# Sheet2.net
KiCad netlist of a schematic drawn in Altium Designer
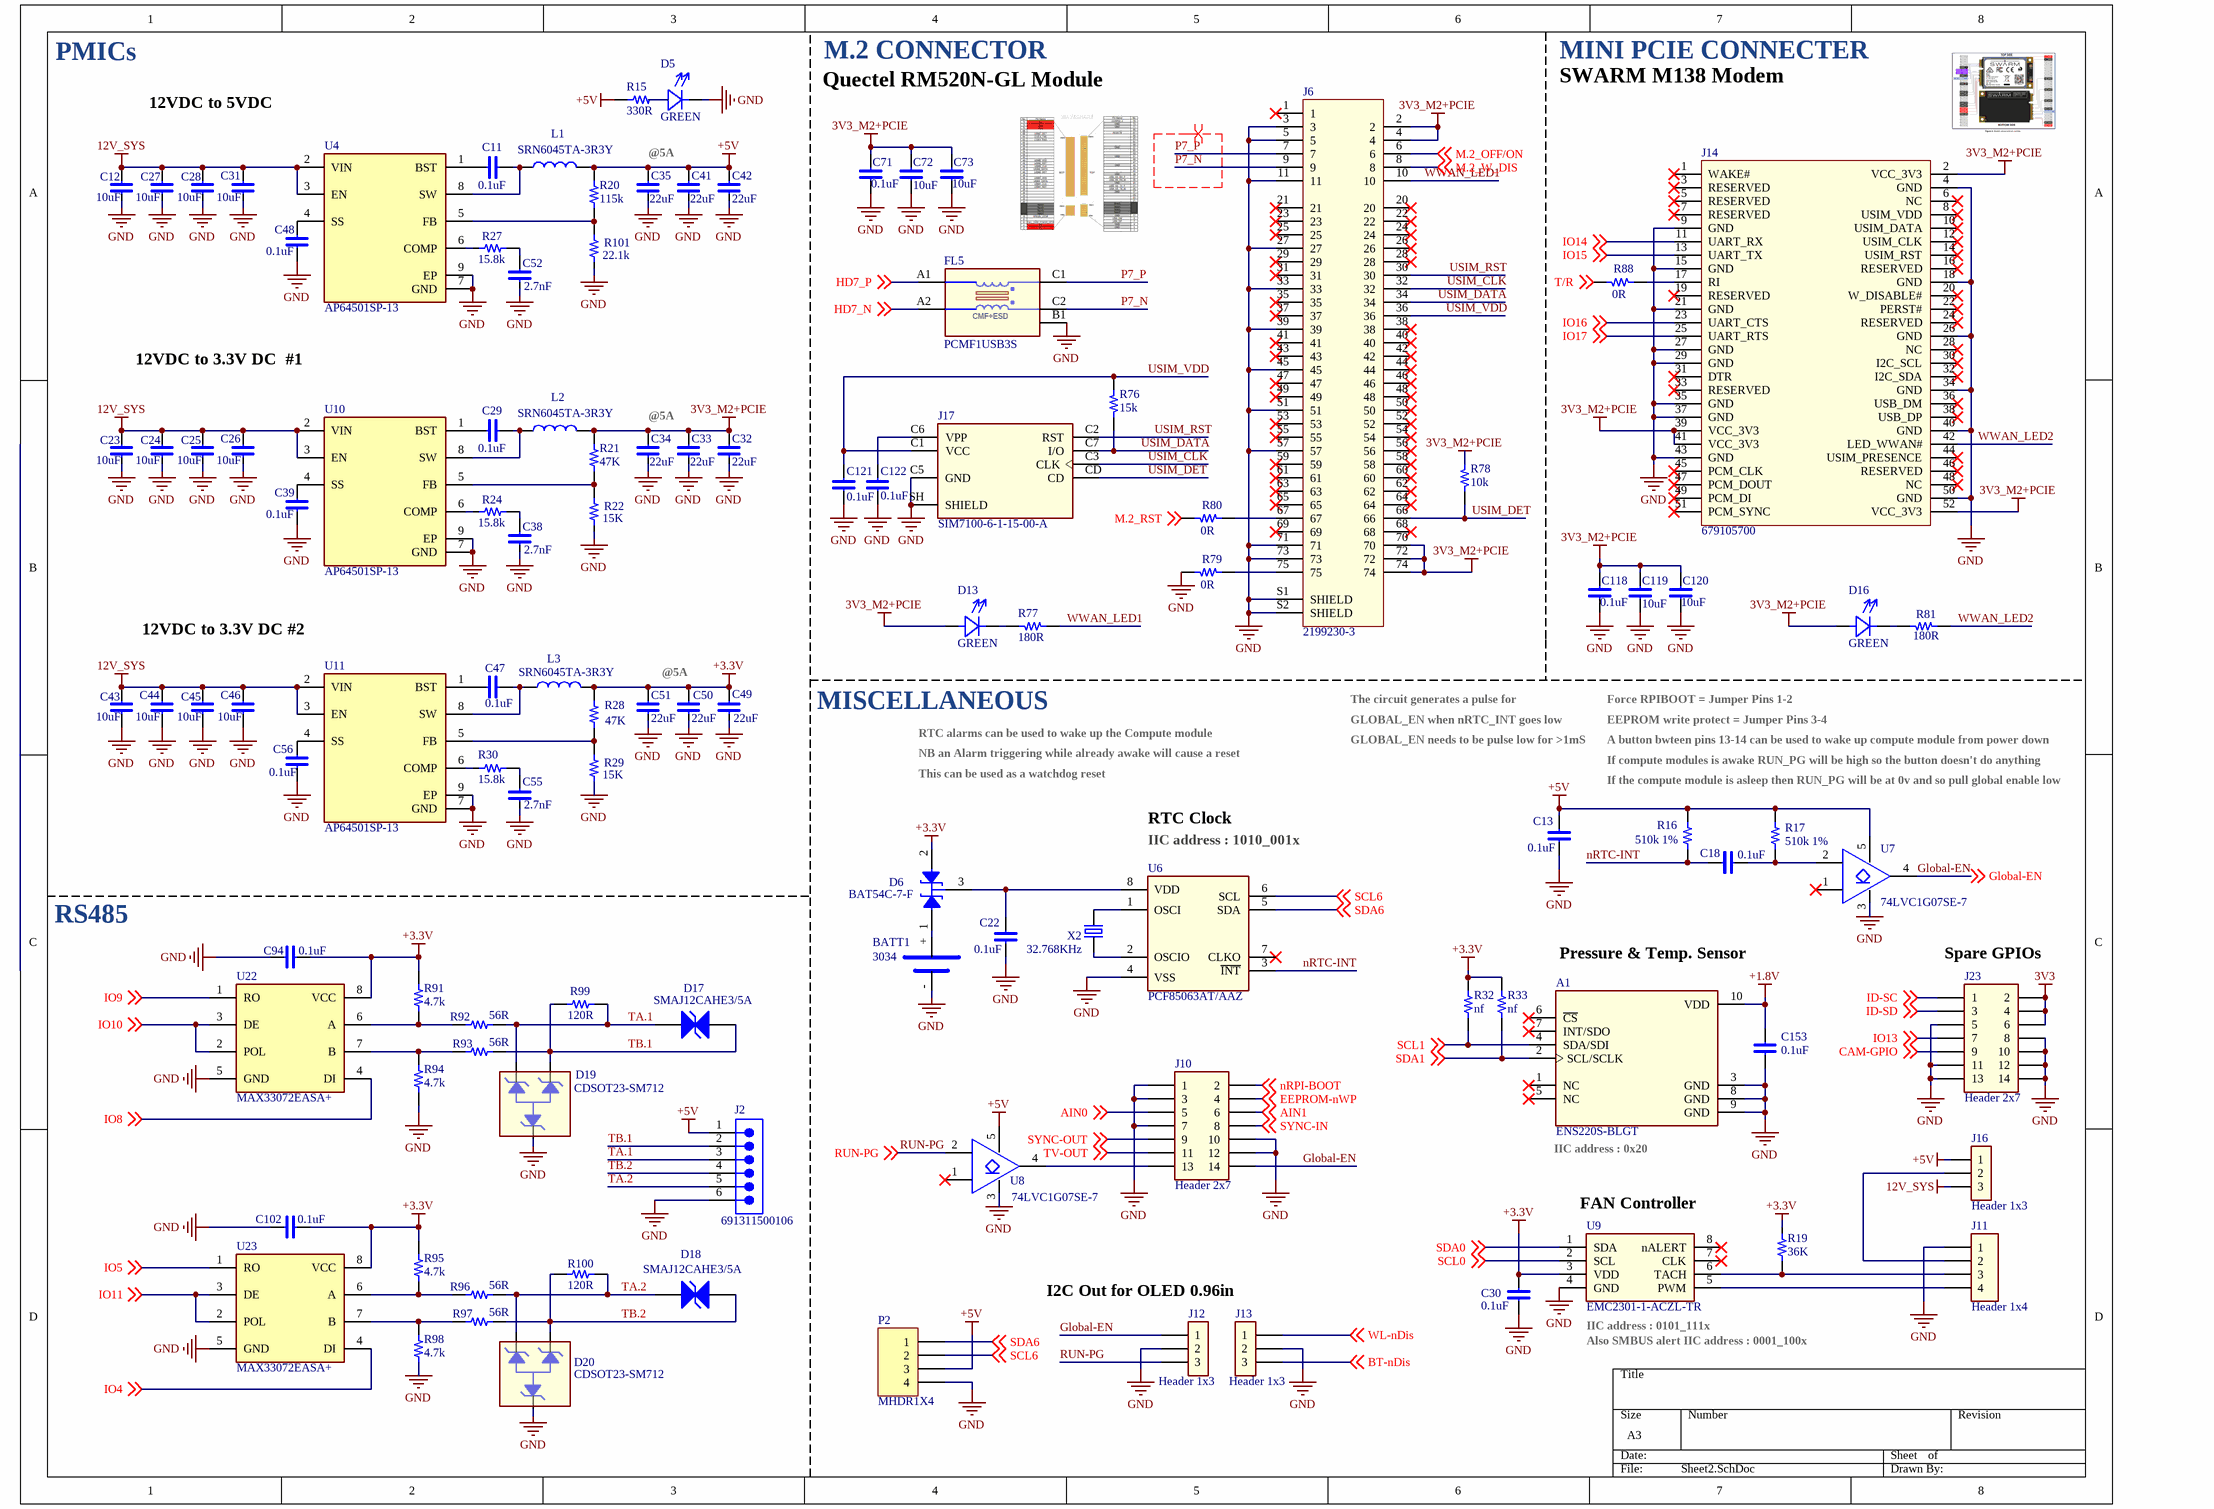
[diagram p0: Sheet2.SchDoc]

(export (version "E")
  (design (tool "Eeschema 10.0.6"))
  (components
    (comp (ref "A1")
      (value "ENS220S-BLGT")
      (footprint "XDCR_ENS220S-BLGT")
      (fields (field (name "MF") "ScioSense"))
      (libsource (lib "ENS220S-BLGT") (part "ENS220S-BLGT"))
    )
    (comp (ref "BATT1")
      (value "3034")
      (footprint "Keystone-3034")
      (description "BATTERY RETAINER COIN 20MM SMD")
      (libsource (lib "Custom_Library") (part "Coin-Cell"))
    )
    (comp (ref "C11")
      (value "0.1uF")
      (footprint "C-0402/1005")
      (description "CAP CER 10UF 25V X5R 1206")
      (fields (field (name "MFR. PART NO.") "C1206C106M3PACTU"))
      (libsource (lib "Custom_Library") (part "CAP 1206/3216"))
    )
    (comp (ref "C12")
      (value "10uF")
      (footprint "C-0805/2012")
      (description "CAP CER 10UF 25V X5R 1206")
      (fields (field (name "MFR. PART NO.") "C1206C106M3PACTU"))
      (libsource (lib "Custom_Library") (part "CAP 1206/3216"))
    )
    (comp (ref "C13")
      (value "0.1uF")
      (footprint "C-0402/1005")
      (description "CAP CER 0.1UF 16V X7R 0402")
      (fields (field (name "MFR. PART NO.") "GCM155R71C104KA55D"))
      (libsource (lib "Custom_Library") (part "Capacitor-NonPolar"))
    )
    (comp (ref "C18")
      (value "0.1uF")
      (footprint "C-0402/1005")
      (description "CAP CER 0.1UF 16V X7R 0402")
      (fields (field (name "MFR. PART NO.") "GCM155R71C104KA55D"))
      (libsource (lib "") (part "Capacitor-NonPolar_1"))
    )
    (comp (ref "C22")
      (value "0.1uF")
      (footprint "C-0402/1005")
      (description "CAP CER 0.1UF 16V X7R 0402")
      (fields (field (name "MFR. PART NO.") "GCM155R71C104KA55D"))
      (libsource (lib "Custom_Library") (part "Capacitor-NonPolar"))
    )
    (comp (ref "C23")
      (value "10uF")
      (footprint "C-0805/2012")
      (description "CAP CER 10UF 25V X5R 1206")
      (fields (field (name "MFR. PART NO.") "C1206C106M3PACTU"))
      (libsource (lib "Custom_Library") (part "CAP 1206/3216"))
    )
    (comp (ref "C24")
      (value "10uF")
      (footprint "C-0805/2012")
      (description "CAP CER 10UF 25V X5R 1206")
      (fields (field (name "MFR. PART NO.") "C1206C106M3PACTU"))
      (libsource (lib "Custom_Library") (part "CAP 1206/3216"))
    )
    (comp (ref "C25")
      (value "10uF")
      (footprint "C-0805/2012")
      (description "CAP CER 10UF 25V X5R 1206")
      (fields (field (name "MFR. PART NO.") "C1206C106M3PACTU"))
      (libsource (lib "Custom_Library") (part "CAP 1206/3216"))
    )
    (comp (ref "C26")
      (value "10uF")
      (footprint "C-0805/2012")
      (description "CAP CER 10UF 25V X5R 1206")
      (fields (field (name "MFR. PART NO.") "C1206C106M3PACTU"))
      (libsource (lib "Custom_Library") (part "CAP 1206/3216"))
    )
    (comp (ref "C27")
      (value "10uF")
      (footprint "C-0805/2012")
      (description "CAP CER 10UF 25V X5R 1206")
      (fields (field (name "MFR. PART NO.") "C1206C106M3PACTU"))
      (libsource (lib "Custom_Library") (part "CAP 1206/3216"))
    )
    (comp (ref "C28")
      (value "10uF")
      (footprint "C-0805/2012")
      (description "CAP CER 10UF 25V X5R 1206")
      (fields (field (name "MFR. PART NO.") "C1206C106M3PACTU"))
      (libsource (lib "Custom_Library") (part "CAP 1206/3216"))
    )
    (comp (ref "C29")
      (value "0.1uF")
      (footprint "C-0402/1005")
      (description "CAP CER 10UF 25V X5R 1206")
      (fields (field (name "MFR. PART NO.") "C1206C106M3PACTU"))
      (libsource (lib "Custom_Library") (part "CAP 1206/3216"))
    )
    (comp (ref "C30")
      (value "0.1uF")
      (footprint "C-0402/1005")
      (description "CAP CER 10UF 25V X5R 1206")
      (fields (field (name "MFR. PART NO.") "C1206C106M3PACTU"))
      (libsource (lib "Custom_Library") (part "CAP 1206/3216"))
    )
    (comp (ref "C31")
      (value "10uF")
      (footprint "C-0805/2012")
      (description "CAP CER 10UF 25V X5R 1206")
      (fields (field (name "MFR. PART NO.") "C1206C106M3PACTU"))
      (libsource (lib "Custom_Library") (part "CAP 1206/3216"))
    )
    (comp (ref "C32")
      (value "22uF")
      (footprint "C-0805/2012")
      (description "CAP CER 10UF 25V X5R 1206")
      (fields (field (name "MFR. PART NO.") "C1206C106M3PACTU"))
      (libsource (lib "") (part "CAP 1206/3216_1"))
    )
    (comp (ref "C33")
      (value "22uF")
      (footprint "C-0805/2012")
      (description "CAP CER 10UF 25V X5R 1206")
      (fields (field (name "MFR. PART NO.") "C1206C106M3PACTU"))
      (libsource (lib "") (part "CAP 1206/3216_1"))
    )
    (comp (ref "C34")
      (value "22uF")
      (footprint "C-0805/2012")
      (description "CAP CER 10UF 25V X5R 1206")
      (fields (field (name "MFR. PART NO.") "C1206C106M3PACTU"))
      (libsource (lib "") (part "CAP 1206/3216_1"))
    )
    (comp (ref "C35")
      (value "22uF")
      (footprint "C-0805/2012")
      (description "CAP CER 10UF 25V X5R 1206")
      (fields (field (name "MFR. PART NO.") "C1206C106M3PACTU"))
      (libsource (lib "") (part "CAP 1206/3216_1"))
    )
    (comp (ref "C38")
      (value "2.7nF")
      (footprint "C-0402/1005")
      (description "CAP CER 10UF 25V X5R 1206")
      (fields (field (name "MFR. PART NO.") "C1206C106M3PACTU"))
      (libsource (lib "Custom_Library") (part "CAP 1206/3216"))
    )
    (comp (ref "C39")
      (value "0.1uF")
      (footprint "C-0402/1005")
      (description "CAP CER 10UF 25V X5R 1206")
      (fields (field (name "MFR. PART NO.") "C1206C106M3PACTU"))
      (libsource (lib "Custom_Library") (part "CAP 1206/3216"))
    )
    (comp (ref "C41")
      (value "22uF")
      (footprint "C-0805/2012")
      (description "CAP CER 10UF 25V X5R 1206")
      (fields (field (name "MFR. PART NO.") "C1206C106M3PACTU"))
      (libsource (lib "") (part "CAP 1206/3216_1"))
    )
    (comp (ref "C42")
      (value "22uF")
      (footprint "C-0805/2012")
      (description "CAP CER 10UF 25V X5R 1206")
      (fields (field (name "MFR. PART NO.") "C1206C106M3PACTU"))
      (libsource (lib "") (part "CAP 1206/3216_1"))
    )
    (comp (ref "C43")
      (value "10uF")
      (footprint "C-0805/2012")
      (description "CAP CER 10UF 25V X5R 1206")
      (fields (field (name "MFR. PART NO.") "C1206C106M3PACTU"))
      (libsource (lib "Custom_Library") (part "CAP 1206/3216"))
    )
    (comp (ref "C44")
      (value "10uF")
      (footprint "C-0805/2012")
      (description "CAP CER 10UF 25V X5R 1206")
      (fields (field (name "MFR. PART NO.") "C1206C106M3PACTU"))
      (libsource (lib "Custom_Library") (part "CAP 1206/3216"))
    )
    (comp (ref "C45")
      (value "10uF")
      (footprint "C-0805/2012")
      (description "CAP CER 10UF 25V X5R 1206")
      (fields (field (name "MFR. PART NO.") "C1206C106M3PACTU"))
      (libsource (lib "Custom_Library") (part "CAP 1206/3216"))
    )
    (comp (ref "C46")
      (value "10uF")
      (footprint "C-0805/2012")
      (description "CAP CER 10UF 25V X5R 1206")
      (fields (field (name "MFR. PART NO.") "C1206C106M3PACTU"))
      (libsource (lib "Custom_Library") (part "CAP 1206/3216"))
    )
    (comp (ref "C47")
      (value "0.1uF")
      (footprint "C-0402/1005")
      (description "CAP CER 10UF 25V X5R 1206")
      (fields (field (name "MFR. PART NO.") "C1206C106M3PACTU"))
      (libsource (lib "Custom_Library") (part "CAP 1206/3216"))
    )
    (comp (ref "C48")
      (value "0.1uF")
      (footprint "C-0402/1005")
      (description "CAP CER 10UF 25V X5R 1206")
      (fields (field (name "MFR. PART NO.") "C1206C106M3PACTU"))
      (libsource (lib "Custom_Library") (part "CAP 1206/3216"))
    )
    (comp (ref "C49")
      (value "22uF")
      (footprint "C-0805/2012")
      (description "CAP CER 10UF 25V X5R 1206")
      (fields (field (name "MFR. PART NO.") "C1206C106M3PACTU"))
      (libsource (lib "") (part "CAP 1206/3216_1"))
    )
    (comp (ref "C50")
      (value "22uF")
      (footprint "C-0805/2012")
      (description "CAP CER 10UF 25V X5R 1206")
      (fields (field (name "MFR. PART NO.") "C1206C106M3PACTU"))
      (libsource (lib "") (part "CAP 1206/3216_1"))
    )
    (comp (ref "C51")
      (value "22uF")
      (footprint "C-0805/2012")
      (description "CAP CER 10UF 25V X5R 1206")
      (fields (field (name "MFR. PART NO.") "C1206C106M3PACTU"))
      (libsource (lib "") (part "CAP 1206/3216_1"))
    )
    (comp (ref "C52")
      (value "2.7nF")
      (footprint "C-0402/1005")
      (description "CAP CER 10UF 25V X5R 1206")
      (fields (field (name "MFR. PART NO.") "C1206C106M3PACTU"))
      (libsource (lib "Custom_Library") (part "CAP 1206/3216"))
    )
    (comp (ref "C55")
      (value "2.7nF")
      (footprint "C-0402/1005")
      (description "CAP CER 10UF 25V X5R 1206")
      (fields (field (name "MFR. PART NO.") "C1206C106M3PACTU"))
      (libsource (lib "Custom_Library") (part "CAP 1206/3216"))
    )
    (comp (ref "C56")
      (value "0.1uF")
      (footprint "C-0402/1005")
      (description "CAP CER 10UF 25V X5R 1206")
      (fields (field (name "MFR. PART NO.") "C1206C106M3PACTU"))
      (libsource (lib "Custom_Library") (part "CAP 1206/3216"))
    )
    (comp (ref "C71")
      (value "0.1uF")
      (footprint "C-0402/1005")
      (description "CAP CER 0.1UF 50V X7R 0402")
      (fields (field (name "MFR. PART NO.") "UMK105B7104KV-FR"))
      (libsource (lib "Custom_Library") (part "Capacitor-NonPolar"))
    )
    (comp (ref "C72")
      (value "10uF")
      (footprint "C-0603/1608")
      (description "CAP CER 0.1UF 50V X7R 0402")
      (fields (field (name "MFR. PART NO.") "UMK105B7104KV-FR"))
      (libsource (lib "Custom_Library") (part "Capacitor-NonPolar"))
    )
    (comp (ref "C73")
      (value "10uF")
      (footprint "C-0603/1608")
      (description "CAP CER 0.1UF 50V X7R 0402")
      (fields (field (name "MFR. PART NO.") "UMK105B7104KV-FR"))
      (libsource (lib "Custom_Library") (part "Capacitor-NonPolar"))
    )
    (comp (ref "C94")
      (value "0.1uF")
      (footprint "C-0402/1005")
      (description "CAP CER 0.1UF 50V X7R 0402")
      (fields (field (name "MFR. PART NO.") "UMK105B7104KV-FR"))
      (libsource (lib "") (part "Capacitor-NonPolar_1"))
    )
    (comp (ref "C102")
      (value "0.1uF")
      (footprint "C-0402/1005")
      (description "CAP CER 0.1UF 50V X7R 0402")
      (fields (field (name "MFR. PART NO.") "UMK105B7104KV-FR"))
      (libsource (lib "") (part "Capacitor-NonPolar_1"))
    )
    (comp (ref "C118")
      (value "0.1uF")
      (footprint "C-0402/1005")
      (description "CAP CER 0.1UF 50V X7R 0402")
      (fields (field (name "MFR. PART NO.") "UMK105B7104KV-FR"))
      (libsource (lib "Custom_Library") (part "Capacitor-NonPolar"))
    )
    (comp (ref "C119")
      (value "10uF")
      (footprint "C-0603/1608")
      (description "CAP CER 0.1UF 50V X7R 0402")
      (fields (field (name "MFR. PART NO.") "UMK105B7104KV-FR"))
      (libsource (lib "Custom_Library") (part "Capacitor-NonPolar"))
    )
    (comp (ref "C120")
      (value "10uF")
      (footprint "C-0603/1608")
      (description "CAP CER 0.1UF 50V X7R 0402")
      (fields (field (name "MFR. PART NO.") "UMK105B7104KV-FR"))
      (libsource (lib "Custom_Library") (part "Capacitor-NonPolar"))
    )
    (comp (ref "C121")
      (value "0.1uF")
      (footprint "C-0402/1005")
      (description "CAP CER 0.1UF 16V X7R 0402")
      (fields (field (name "MFR. PART NO.") "GCM155R71C104KA55D"))
      (libsource (lib "Custom_Library") (part "Capacitor-NonPolar"))
    )
    (comp (ref "C122")
      (value "0.1uF")
      (footprint "C-0402/1005")
      (description "CAP CER 0.1UF 16V X7R 0402")
      (fields (field (name "MFR. PART NO.") "GCM155R71C104KA55D"))
      (libsource (lib "Custom_Library") (part "Capacitor-NonPolar"))
    )
    (comp (ref "C153")
      (value "0.1uF")
      (footprint "C-0402/1005")
      (description "CAP CER 0.1UF 16V X7R 0402")
      (fields (field (name "MFR. PART NO.") "GCM155R71C104KA55D"))
      (libsource (lib "Custom_Library") (part "Capacitor-NonPolar"))
    )
    (comp (ref "D5")
      (value "GREEN")
      (footprint "LED-0603-Green")
      (libsource (lib "Custom_Library") (part "Diode-LED"))
    )
    (comp (ref "D6")
      (value "BAT54C-7-F")
      (footprint "SOT-23-3")
      (description "DIODE ARRAY SCHOTTKY 30V SOT23-3")
      (libsource (lib "Custom_Library") (part "BAT54C-7-F"))
    )
    (comp (ref "D13") (value "GREEN") (footprint "LED-0402-GREEN") (libsource (lib "") (part "Diode-LED_1")))
    (comp (ref "D16") (value "GREEN") (footprint "LED-0402-GREEN") (libsource (lib "") (part "Diode-LED_1")))
    (comp (ref "D17")
      (value "SMAJ12CAHE3/5A")
      (footprint "VISH-DO-214AC-2_L")
      (fields (field (name "MANUFACTURER") "Vishay Semiconductor"))
      (libsource (lib "Altium Content Vault") (part "VISH-A1A2-2"))
    )
    (comp (ref "D18")
      (value "SMAJ12CAHE3/5A")
      (footprint "VISH-DO-214AC-2_L")
      (fields (field (name "MANUFACTURER") "Vishay Semiconductor"))
      (libsource (lib "Altium Content Vault") (part "VISH-A1A2-2"))
    )
    (comp (ref "D19")
      (value "CDSOT23-SM712")
      (footprint "SOT-23-3")
      (description "TVS DIODE 3.5V 6.5V SLP1006N3T")
      (fields (field (name "MFR. PART NO.") "RCLAMP3552T.TNT"))
      (libsource (lib "Custom_Library") (part "RCLAMP3552T"))
    )
    (comp (ref "D20")
      (value "CDSOT23-SM712")
      (footprint "SOT-23-3")
      (description "TVS DIODE 3.5V 6.5V SLP1006N3T")
      (fields (field (name "MFR. PART NO.") "RCLAMP3552T.TNT"))
      (libsource (lib "Custom_Library") (part "RCLAMP3552T"))
    )
    (comp (ref "FL5")
      (value "PCMF1USB3S")
      (footprint "WLCSP5(2-1-2)_NEX")
      (description "FLT, SMT, WLCSP5, Common Mode EMI Filters")
      (fields (field (name "MANUFACTURER") "Nexperia"))
      (libsource (lib "Ewikenheiser_CM4_Board_V2") (part "Nexperia, PCMF1USB3SZ"))
    )
    (comp (ref "J2")
      (value "691311500106")
      (footprint "691311500106")
      (fields (field (name "VOLTAGE") "300V"))
      (libsource (lib "Altium Content Vault") (part "TBL - 1R - 06P - Male"))
    )
    (comp (ref "J6")
      (value "2199230-3")
      (footprint "TE_2199230-3")
      (description "M.2 0.5PITCH 4.2H KEY B 15U'' AU")
      (libsource (lib "2199230-3") (part "2199230-3"))
    )
    (comp (ref "J10")
      (value "Header 2x7")
      (footprint "PIN HEADER 2x7 2.54mm")
      (description "CONN HEADER VERT 14POS 2.54MM")
      (fields (field (name "MFR. PART NO.") "PRPC007DFBN-RC"))
      (libsource (lib "Custom_Library") (part "Header 2x7"))
    )
    (comp (ref "J11")
      (value "Header 1x4")
      (footprint "PIN HEADER 1x4 2.54mm")
      (description "CONN HEADER VERT 4POS 2.54MM")
      (libsource (lib "Custom_Library") (part "Header 1x4"))
    )
    (comp (ref "J12")
      (value "Header 1x3")
      (footprint "PIN HEADER 1x3 2.54mm")
      (description "CONN HEADER VERT 3POS 2.54MM")
      (fields (field (name "MFR. PART NO.") "75160-156-03LF"))
      (libsource (lib "Custom_Library") (part "Header 1x3"))
    )
    (comp (ref "J13")
      (value "Header 1x3")
      (footprint "PIN HEADER 1x3 2.54mm")
      (description "CONN HEADER VERT 3POS 2.54MM")
      (fields (field (name "MFR. PART NO.") "75160-156-03LF"))
      (libsource (lib "") (part "Header 1x3_1"))
    )
    (comp (ref "J14")
      (value "679105700")
      (footprint "679105700-A")
      (libsource (lib "Schlib2") (part "Component_1"))
    )
    (comp (ref "J16")
      (value "Header 1x3")
      (footprint "PIN HEADER 1x3 2.54mm")
      (description "CONN HEADER VERT 3POS 2.54MM")
      (fields (field (name "MFR. PART NO.") "75160-156-03LF"))
      (libsource (lib "Custom_Library") (part "Header 1x3"))
    )
    (comp (ref "J17")
      (value "SIM7100-6-1-15-00-A")
      (footprint "GCT_SIM7100-6-1-15-00-A_REVC")
      (description "7 _6 + 1_ Position Card Connector Micro SIM Surface Mount, Right Angle Gold")
      (fields (field (name "MF") "Global Connector Technology"))
      (libsource (lib "SnapEDAsch") (part "SIM7100-6-1-15-00-A_REVC"))
    )
    (comp (ref "J23")
      (value "Header 2x7")
      (footprint "PIN HEADER 2x7 2.54mm")
      (description "CONN HEADER VERT 14POS 2.54MM")
      (fields (field (name "MFR. PART NO.") "PRPC007DFBN-RC"))
      (libsource (lib "Custom_Library") (part "Header 2x7"))
    )
    (comp (ref "L1")
      (value "SRN6045TA-3R3Y")
      (footprint "IND_SRN6045TA-3R3Y")
      (description "FIXED IND 22UH 620MA 350 MOHM")
      (fields (field (name "MFR. PART NO.") "ASPI-4020S-220M-T"))
      (libsource (lib "Custom_Library") (part "4.3x4.3mm"))
    )
    (comp (ref "L2")
      (value "SRN6045TA-3R3Y")
      (footprint "IND_SRN6045TA-3R3Y")
      (description "FIXED IND 22UH 620MA 350 MOHM")
      (fields (field (name "MFR. PART NO.") "ASPI-4020S-220M-T"))
      (libsource (lib "Custom_Library") (part "4.3x4.3mm"))
    )
    (comp (ref "L3")
      (value "SRN6045TA-3R3Y")
      (footprint "IND_SRN6045TA-3R3Y")
      (description "FIXED IND 22UH 620MA 350 MOHM")
      (fields (field (name "MFR. PART NO.") "ASPI-4020S-220M-T"))
      (libsource (lib "Custom_Library") (part "4.3x4.3mm"))
    )
    (comp (ref "P2")
      (value "MHDR1X4")
      (footprint "PIN HEADER 1x4 2.54mm")
      (description "Header, 4-Pin")
      (fields (field (name "PUBLISHER") "Altium Limited"))
      (libsource (lib "Miscellaneous Connectors") (part "MHDR1X4"))
    )
    (comp (ref "R15")
      (value "330R")
      (footprint "R-0402/1005")
      (description "RES SMD 51 OHM 0.5% 1/16W 0402")
      (fields (field (name "MFR. PART NO.") "ERA-2AED510X"))
      (libsource (lib "Custom_Library") (part "Resistor"))
    )
    (comp (ref "R16")
      (value "510k 1%")
      (footprint "R-0402/1005")
      (description "RES SMD 510K OHM 1% 1/16W 0402")
      (fields (field (name "MFR. PART NO.") "MCR01MZPF5103"))
      (libsource (lib "Custom_Library") (part "Resistor"))
    )
    (comp (ref "R17")
      (value "510k 1%")
      (footprint "R-0402/1005")
      (description "RES SMD 510K OHM 1% 1/16W 0402")
      (fields (field (name "MFR. PART NO.") "MCR01MZPF5103"))
      (libsource (lib "Custom_Library") (part "Resistor"))
    )
    (comp (ref "R19")
      (value "36K")
      (footprint "R-0402/1005")
      (description "RES SMD 51 OHM 0.5% 1/16W 0402")
      (fields (field (name "MFR. PART NO.") "ERA-2AED510X"))
      (libsource (lib "Custom_Library") (part "Resistor"))
    )
    (comp (ref "R20")
      (value "115k")
      (footprint "R-0402/1005")
      (description "RES SMD 51 OHM 0.5% 1/16W 0402")
      (fields (field (name "MFR. PART NO.") "ERA-2AED510X"))
      (libsource (lib "Custom_Library") (part "Resistor"))
    )
    (comp (ref "R21")
      (value "47K")
      (footprint "R-0402/1005")
      (description "RES SMD 51 OHM 0.5% 1/16W 0402")
      (fields (field (name "MFR. PART NO.") "ERA-2AED510X"))
      (libsource (lib "Custom_Library") (part "Resistor"))
    )
    (comp (ref "R22")
      (value "15K")
      (footprint "R-0402/1005")
      (description "RES SMD 51 OHM 0.5% 1/16W 0402")
      (fields (field (name "MFR. PART NO.") "ERA-2AED510X"))
      (libsource (lib "Custom_Library") (part "Resistor"))
    )
    (comp (ref "R24")
      (value "15.8k")
      (footprint "R-0402/1005")
      (description "RES SMD 51 OHM 0.5% 1/16W 0402")
      (fields (field (name "MFR. PART NO.") "ERA-2AED510X"))
      (libsource (lib "Custom_Library") (part "Resistor"))
    )
    (comp (ref "R27")
      (value "15.8k")
      (footprint "R-0402/1005")
      (description "RES SMD 51 OHM 0.5% 1/16W 0402")
      (fields (field (name "MFR. PART NO.") "ERA-2AED510X"))
      (libsource (lib "Custom_Library") (part "Resistor"))
    )
    (comp (ref "R28")
      (value "47K")
      (footprint "R-0402/1005")
      (description "RES SMD 51 OHM 0.5% 1/16W 0402")
      (fields (field (name "MFR. PART NO.") "ERA-2AED510X"))
      (libsource (lib "Custom_Library") (part "Resistor"))
    )
    (comp (ref "R29")
      (value "15K")
      (footprint "R-0402/1005")
      (description "RES SMD 51 OHM 0.5% 1/16W 0402")
      (fields (field (name "MFR. PART NO.") "ERA-2AED510X"))
      (libsource (lib "Custom_Library") (part "Resistor"))
    )
    (comp (ref "R30")
      (value "15.8k")
      (footprint "R-0402/1005")
      (description "RES SMD 51 OHM 0.5% 1/16W 0402")
      (fields (field (name "MFR. PART NO.") "ERA-2AED510X"))
      (libsource (lib "Custom_Library") (part "Resistor"))
    )
    (comp (ref "R32")
      (value "nf")
      (footprint "R-0402/1005")
      (description "RES SMD 1K OHM 1% 1/16W 0402")
      (fields (field (name "MFR. PART NO.") "RC0402FR-071KL"))
      (libsource (lib "Custom_Library") (part "Resistor"))
    )
    (comp (ref "R33")
      (value "nf")
      (footprint "R-0402/1005")
      (description "RES SMD 1K OHM 1% 1/16W 0402")
      (fields (field (name "MFR. PART NO.") "RC0402FR-071KL"))
      (libsource (lib "Custom_Library") (part "Resistor"))
    )
    (comp (ref "R76")
      (value "15k")
      (footprint "R-0402/1005")
      (description "RES SMD 51 OHM 0.5% 1/16W 0402")
      (fields (field (name "MFR. PART NO.") "ERA-2AED510X"))
      (libsource (lib "Custom_Library") (part "Resistor"))
    )
    (comp (ref "R77")
      (value "180R")
      (footprint "R-0402/1005")
      (description "RES SMD 51 OHM 0.5% 1/16W 0402")
      (fields (field (name "MFR. PART NO.") "ERA-2AED510X"))
      (libsource (lib "Custom_Library") (part "Resistor"))
    )
    (comp (ref "R78")
      (value "10k")
      (footprint "R-0402/1005")
      (description "RES SMD 51 OHM 0.5% 1/16W 0402")
      (fields (field (name "MFR. PART NO.") "ERA-2AED510X"))
      (libsource (lib "Custom_Library") (part "Resistor"))
    )
    (comp (ref "R79")
      (value "0R")
      (footprint "R-0402/1005")
      (description "RES SMD 51 OHM 0.5% 1/16W 0402")
      (fields (field (name "MFR. PART NO.") "ERA-2AED510X"))
      (libsource (lib "Custom_Library") (part "Resistor"))
    )
    (comp (ref "R80")
      (value "0R")
      (footprint "R-0402/1005")
      (description "RES SMD 51 OHM 0.5% 1/16W 0402")
      (fields (field (name "MFR. PART NO.") "ERA-2AED510X"))
      (libsource (lib "Custom_Library") (part "Resistor"))
    )
    (comp (ref "R81")
      (value "180R")
      (footprint "R-0402/1005")
      (description "RES SMD 51 OHM 0.5% 1/16W 0402")
      (fields (field (name "MFR. PART NO.") "ERA-2AED510X"))
      (libsource (lib "Custom_Library") (part "Resistor"))
    )
    (comp (ref "R88")
      (value "0R")
      (footprint "R-0402/1005")
      (description "RES SMD 51 OHM 0.5% 1/16W 0402")
      (fields (field (name "MFR. PART NO.") "ERA-2AED510X"))
      (libsource (lib "Custom_Library") (part "Resistor"))
    )
    (comp (ref "R91")
      (value "4.7k")
      (footprint "R-0402/1005")
      (description "RES SMD 51 OHM 0.5% 1/16W 0402")
      (fields (field (name "MFR. PART NO.") "ERA-2AED510X"))
      (libsource (lib "Custom_Library") (part "Resistor"))
    )
    (comp (ref "R92")
      (value "56R")
      (footprint "R-0402/1005")
      (description "RES SMD 51 OHM 0.5% 1/16W 0402")
      (fields (field (name "MFR. PART NO.") "ERA-2AED510X"))
      (libsource (lib "Custom_Library") (part "Resistor"))
    )
    (comp (ref "R93")
      (value "56R")
      (footprint "R-0402/1005")
      (description "RES SMD 51 OHM 0.5% 1/16W 0402")
      (fields (field (name "MFR. PART NO.") "ERA-2AED510X"))
      (libsource (lib "Custom_Library") (part "Resistor"))
    )
    (comp (ref "R94")
      (value "4.7k")
      (footprint "R-0402/1005")
      (description "RES SMD 51 OHM 0.5% 1/16W 0402")
      (fields (field (name "MFR. PART NO.") "ERA-2AED510X"))
      (libsource (lib "Custom_Library") (part "Resistor"))
    )
    (comp (ref "R95")
      (value "4.7k")
      (footprint "R-0402/1005")
      (description "RES SMD 51 OHM 0.5% 1/16W 0402")
      (fields (field (name "MFR. PART NO.") "ERA-2AED510X"))
      (libsource (lib "Custom_Library") (part "Resistor"))
    )
    (comp (ref "R96")
      (value "56R")
      (footprint "R-0402/1005")
      (description "RES SMD 51 OHM 0.5% 1/16W 0402")
      (fields (field (name "MFR. PART NO.") "ERA-2AED510X"))
      (libsource (lib "Custom_Library") (part "Resistor"))
    )
    (comp (ref "R97")
      (value "56R")
      (footprint "R-0402/1005")
      (description "RES SMD 51 OHM 0.5% 1/16W 0402")
      (fields (field (name "MFR. PART NO.") "ERA-2AED510X"))
      (libsource (lib "Custom_Library") (part "Resistor"))
    )
    (comp (ref "R98")
      (value "4.7k")
      (footprint "R-0402/1005")
      (description "RES SMD 51 OHM 0.5% 1/16W 0402")
      (fields (field (name "MFR. PART NO.") "ERA-2AED510X"))
      (libsource (lib "Custom_Library") (part "Resistor"))
    )
    (comp (ref "R99")
      (value "120R")
      (footprint "R-0402/1005")
      (description "RES SMD 51 OHM 0.5% 1/16W 0402")
      (fields (field (name "MFR. PART NO.") "ERA-2AED510X"))
      (libsource (lib "Custom_Library") (part "Resistor"))
    )
    (comp (ref "R100")
      (value "120R")
      (footprint "R-0402/1005")
      (description "RES SMD 51 OHM 0.5% 1/16W 0402")
      (fields (field (name "MFR. PART NO.") "ERA-2AED510X"))
      (libsource (lib "Custom_Library") (part "Resistor"))
    )
    (comp (ref "R101")
      (value "22.1k")
      (footprint "R-0402/1005")
      (description "RES SMD 51 OHM 0.5% 1/16W 0402")
      (fields (field (name "MFR. PART NO.") "ERA-2AED510X"))
      (libsource (lib "Custom_Library") (part "Resistor"))
    )
    (comp (ref "U4")
      (value "AP64501SP-13")
      (footprint "FP-SO-8EP-IPC_A")
      (description "DCDC CONV HV BUCK SO-8EP")
      (libsource (lib "Altium Content Vault") (part "5ebf8146ffb11b38024cfc6b6736e1a"))
    )
    (comp (ref "U6")
      (value "PCF85063AT/AAZ")
      (footprint "SOIC-8 (W3.9mm)")
      (description "IC RTC CLK/CALENDAR I2C 8SOIC")
      (libsource (lib "Custom_Library") (part "PCF85063AT/AAZ"))
    )
    (comp (ref "U7")
      (value "74LVC1G07SE-7")
      (footprint "SOT-353")
      (description "IC BUF NON-INVERT 5.5V SOT353")
      (libsource (lib "Custom_Library") (part "74LVC1G07SE-7"))
    )
    (comp (ref "U8")
      (value "74LVC1G07SE-7")
      (footprint "SOT-353")
      (description "IC BUF NON-INVERT 5.5V SOT353")
      (libsource (lib "Custom_Library") (part "74LVC1G07SE-7"))
    )
    (comp (ref "U9")
      (value "EMC2301-1-ACZL-TR")
      (footprint "SOP65P490X110-8N")
      (libsource (lib "Schlib1") (part "Component_1"))
    )
    (comp (ref "U10")
      (value "AP64501SP-13")
      (footprint "FP-SO-8EP-IPC_A")
      (description "DCDC CONV HV BUCK SO-8EP")
      (libsource (lib "Altium Content Vault") (part "5ebf8146ffb11b38024cfc6b6736e1a"))
    )
    (comp (ref "U11")
      (value "AP64501SP-13")
      (footprint "FP-SO-8EP-IPC_A")
      (description "DCDC CONV HV BUCK SO-8EP")
      (libsource (lib "Altium Content Vault") (part "5ebf8146ffb11b38024cfc6b6736e1a"))
    )
    (comp (ref "U22")
      (value "MAX33072EASA+")
      (footprint "FP-S8-4-IPC_B")
      (description "DUAL VOLTAGE RS-485, 70V FP, 40V")
      (libsource (lib "Altium Content Vault") (part "a5c5425fa9c34ba518155519c74f6dd"))
    )
    (comp (ref "U23")
      (value "MAX33072EASA+")
      (footprint "FP-S8-4-IPC_B")
      (description "DUAL VOLTAGE RS-485, 70V FP, 40V")
      (libsource (lib "Altium Content Vault") (part "a5c5425fa9c34ba518155519c74f6dd"))
    )
    (comp (ref "X2")
      (value "32.768KHz")
      (footprint "XTAL3215")
      (description "CRYSTAL 32.7680KHZ 7PF SMD 20ppm")
      (fields (field (name "MFR. PART NO.") "CM7V-T1A-32.768KHZ-7PF-20PPM-TB-QA"))
      (libsource (lib "Oscilators") (part "ST3215SB32768C0HPWBB"))
    )
  )
  (nets
    (net (code "1") (name "+1.8V") (class "Default")
      (node (ref "A1") (pin "10") (pinfunction "VDD_10") (pintype "passive"))
      (node (ref "C153") (pin "1") (pinfunction "1_1") (pintype "passive"))
    )
    (net (code "2") (name "+3.3V") (class "Default")
      (node (ref "C102") (pin "2") (pinfunction "2_2") (pintype "passive"))
      (node (ref "C30") (pin "1") (pinfunction "1_1") (pintype "passive"))
      (node (ref "C49") (pin "1") (pinfunction "1_1") (pintype "passive"))
      (node (ref "C50") (pin "1") (pinfunction "1_1") (pintype "passive"))
      (node (ref "C51") (pin "1") (pinfunction "1_1") (pintype "passive"))
      (node (ref "C94") (pin "2") (pinfunction "2_2") (pintype "passive"))
      (node (ref "D6") (pin "2") (pinfunction "2_2") (pintype "passive"))
      (node (ref "L3") (pin "1") (pinfunction "1_1") (pintype "passive"))
      (node (ref "R19") (pin "1") (pinfunction "1_1") (pintype "passive"))
      (node (ref "R28") (pin "1") (pinfunction "1_1") (pintype "passive"))
      (node (ref "R32") (pin "1") (pinfunction "1_1") (pintype "passive"))
      (node (ref "R33") (pin "1") (pinfunction "1_1") (pintype "passive"))
      (node (ref "R91") (pin "2") (pinfunction "2_2") (pintype "passive"))
      (node (ref "R95") (pin "2") (pinfunction "2_2") (pintype "passive"))
      (node (ref "U22") (pin "8") (pinfunction "VCC_8") (pintype "passive"))
      (node (ref "U23") (pin "8") (pinfunction "VCC_8") (pintype "passive"))
      (node (ref "U9") (pin "3") (pinfunction "VDD_3") (pintype "passive"))
    )
    (net (code "3") (name "+5V") (class "Default")
      (node (ref "C13") (pin "1") (pinfunction "1_1") (pintype "passive"))
      (node (ref "C35") (pin "1") (pinfunction "1_1") (pintype "passive"))
      (node (ref "C41") (pin "1") (pinfunction "1_1") (pintype "passive"))
      (node (ref "C42") (pin "1") (pinfunction "1_1") (pintype "passive"))
      (node (ref "J16") (pin "1") (pinfunction "1_1") (pintype "passive"))
      (node (ref "J2") (pin "1") (pinfunction "1_1") (pintype "passive"))
      (node (ref "L1") (pin "1") (pinfunction "1_1") (pintype "passive"))
      (node (ref "P2") (pin "3") (pinfunction "3_3") (pintype "passive"))
      (node (ref "R15") (pin "2") (pinfunction "2_2") (pintype "passive"))
      (node (ref "R16") (pin "2") (pinfunction "2_2") (pintype "passive"))
      (node (ref "R17") (pin "2") (pinfunction "2_2") (pintype "passive"))
      (node (ref "R20") (pin "1") (pinfunction "1_1") (pintype "passive"))
      (node (ref "U7") (pin "5") (pinfunction "5_5") (pintype "passive"))
      (node (ref "U8") (pin "5") (pinfunction "5_5") (pintype "passive"))
    )
    (net (code "4") (name "/P7_N") (class "Default")
      (node (ref "FL5") (pin "C2") (pinfunction "CH1_OUT-_C2") (pintype "passive"))
      (node (ref "J6") (pin "9") (pinfunction "9_9") (pintype "passive"))
    )
    (net (code "5") (name "/P7_P") (class "Default")
      (node (ref "FL5") (pin "C1") (pinfunction "CH1_OUT+_C1") (pintype "passive"))
      (node (ref "J6") (pin "7") (pinfunction "7_7") (pintype "passive"))
    )
    (net (code "6") (name "/TA.1") (class "Default")
      (node (ref "D17") (pin "1") (pinfunction "A1_1") (pintype "passive"))
      (node (ref "D19") (pin "1") (pinfunction "1_1") (pintype "passive"))
      (node (ref "J2") (pin "3") (pinfunction "3_3") (pintype "passive"))
      (node (ref "R92") (pin "2") (pinfunction "2_2") (pintype "passive"))
      (node (ref "R99") (pin "1") (pinfunction "1_1") (pintype "passive"))
    )
    (net (code "7") (name "/TA.2") (class "Default")
      (node (ref "D18") (pin "1") (pinfunction "A1_1") (pintype "passive"))
      (node (ref "D20") (pin "1") (pinfunction "1_1") (pintype "passive"))
      (node (ref "J2") (pin "5") (pinfunction "5_5") (pintype "passive"))
      (node (ref "R100") (pin "1") (pinfunction "1_1") (pintype "passive"))
      (node (ref "R96") (pin "2") (pinfunction "2_2") (pintype "passive"))
    )
    (net (code "8") (name "/TB.1") (class "Default")
      (node (ref "D17") (pin "2") (pinfunction "A2_2") (pintype "passive"))
      (node (ref "D19") (pin "2") (pinfunction "2_2") (pintype "passive"))
      (node (ref "J2") (pin "2") (pinfunction "2_2") (pintype "passive"))
      (node (ref "R93") (pin "2") (pinfunction "2_2") (pintype "passive"))
      (node (ref "R99") (pin "2") (pinfunction "2_2") (pintype "passive"))
    )
    (net (code "9") (name "/TB.2") (class "Default")
      (node (ref "D18") (pin "2") (pinfunction "A2_2") (pintype "passive"))
      (node (ref "D20") (pin "2") (pinfunction "2_2") (pintype "passive"))
      (node (ref "J2") (pin "4") (pinfunction "4_4") (pintype "passive"))
      (node (ref "R100") (pin "2") (pinfunction "2_2") (pintype "passive"))
      (node (ref "R97") (pin "2") (pinfunction "2_2") (pintype "passive"))
    )
    (net (code "10") (name "/USIM_CLK") (class "Default")
      (node (ref "J17") (pin "C3") (pinfunction "CLK_C3") (pintype "passive"))
      (node (ref "J6") (pin "32") (pinfunction "32_32") (pintype "passive"))
    )
    (net (code "11") (name "/USIM_DATA") (class "Default")
      (node (ref "J17") (pin "C7") (pinfunction "I/O_C7") (pintype "passive"))
      (node (ref "J6") (pin "34") (pinfunction "34_34") (pintype "passive"))
      (node (ref "R76") (pin "1") (pinfunction "1_1") (pintype "passive"))
    )
    (net (code "12") (name "/USIM_DET") (class "Default")
      (node (ref "J17") (pin "CD") (pinfunction "CD_CD") (pintype "passive"))
      (node (ref "J6") (pin "66") (pinfunction "66_66") (pintype "passive"))
      (node (ref "R78") (pin "1") (pinfunction "1_1") (pintype "passive"))
    )
    (net (code "13") (name "/USIM_RST") (class "Default")
      (node (ref "J17") (pin "C2") (pinfunction "RST_C2") (pintype "passive"))
      (node (ref "J6") (pin "30") (pinfunction "30_30") (pintype "passive"))
    )
    (net (code "14") (name "/USIM_VDD") (class "Default")
      (node (ref "C121") (pin "1") (pinfunction "1_1") (pintype "passive"))
      (node (ref "J17") (pin "C1") (pinfunction "VCC_C1") (pintype "passive"))
      (node (ref "J6") (pin "36") (pinfunction "36_36") (pintype "passive"))
      (node (ref "R76") (pin "2") (pinfunction "2_2") (pintype "passive"))
    )
    (net (code "15") (name "/WWAN_LED1") (class "Default")
      (node (ref "J6") (pin "10") (pinfunction "10_10") (pintype "passive"))
      (node (ref "R77") (pin "1") (pinfunction "1_1") (pintype "passive"))
    )
    (net (code "16") (name "/WWAN_LED2") (class "Default")
      (node (ref "J14") (pin "42") (pinfunction "LED_WWAN#_42") (pintype "passive"))
      (node (ref "R81") (pin "1") (pinfunction "1_1") (pintype "passive"))
    )
    (net (code "17") (name "/nRTC-INT") (class "Default")
      (node (ref "C18") (pin "1") (pinfunction "1_1") (pintype "passive"))
      (node (ref "R16") (pin "1") (pinfunction "1_1") (pintype "passive"))
      (node (ref "U6") (pin "3") (pinfunction "~{INT}_3") (pintype "passive"))
    )
    (net (code "18") (name "3V3") (class "Default")
      (node (ref "J23") (pin "2") (pinfunction "2_2") (pintype "passive"))
      (node (ref "J23") (pin "4") (pinfunction "4_4") (pintype "passive"))
      (node (ref "J23") (pin "6") (pinfunction "6_6") (pintype "passive"))
    )
    (net (code "19") (name "3V3_M2+PCIE") (class "Default")
      (node (ref "C118") (pin "1") (pinfunction "1_1") (pintype "passive"))
      (node (ref "C119") (pin "1") (pinfunction "1_1") (pintype "passive"))
      (node (ref "C120") (pin "1") (pinfunction "1_1") (pintype "passive"))
      (node (ref "C32") (pin "1") (pinfunction "1_1") (pintype "passive"))
      (node (ref "C33") (pin "1") (pinfunction "1_1") (pintype "passive"))
      (node (ref "C34") (pin "1") (pinfunction "1_1") (pintype "passive"))
      (node (ref "C71") (pin "1") (pinfunction "1_1") (pintype "passive"))
      (node (ref "C72") (pin "1") (pinfunction "1_1") (pintype "passive"))
      (node (ref "C73") (pin "1") (pinfunction "1_1") (pintype "passive"))
      (node (ref "D13") (pin "1") (pinfunction "A_1") (pintype "passive"))
      (node (ref "D16") (pin "1") (pinfunction "A_1") (pintype "passive"))
      (node (ref "J14") (pin "2") (pinfunction "VCC_3V3_2") (pintype "passive"))
      (node (ref "J14") (pin "39") (pinfunction "VCC_3V3_39") (pintype "passive"))
      (node (ref "J14") (pin "41") (pinfunction "VCC_3V3_41") (pintype "passive"))
      (node (ref "J14") (pin "52") (pinfunction "VCC_3V3_52") (pintype "passive"))
      (node (ref "J6") (pin "2") (pinfunction "2_2") (pintype "passive"))
      (node (ref "J6") (pin "4") (pinfunction "4_4") (pintype "passive"))
      (node (ref "J6") (pin "70") (pinfunction "70_70") (pintype "passive"))
      (node (ref "J6") (pin "72") (pinfunction "72_72") (pintype "passive"))
      (node (ref "J6") (pin "74") (pinfunction "74_74") (pintype "passive"))
      (node (ref "L2") (pin "1") (pinfunction "1_1") (pintype "passive"))
      (node (ref "R21") (pin "1") (pinfunction "1_1") (pintype "passive"))
      (node (ref "R78") (pin "2") (pinfunction "2_2") (pintype "passive"))
    )
    (net (code "20") (name "12V_SYS") (class "Default")
      (node (ref "C12") (pin "1") (pinfunction "1_1") (pintype "passive"))
      (node (ref "C23") (pin "1") (pinfunction "1_1") (pintype "passive"))
      (node (ref "C24") (pin "1") (pinfunction "1_1") (pintype "passive"))
      (node (ref "C25") (pin "1") (pinfunction "1_1") (pintype "passive"))
      (node (ref "C26") (pin "1") (pinfunction "1_1") (pintype "passive"))
      (node (ref "C27") (pin "1") (pinfunction "1_1") (pintype "passive"))
      (node (ref "C28") (pin "1") (pinfunction "1_1") (pintype "passive"))
      (node (ref "C31") (pin "1") (pinfunction "1_1") (pintype "passive"))
      (node (ref "C43") (pin "1") (pinfunction "1_1") (pintype "passive"))
      (node (ref "C44") (pin "1") (pinfunction "1_1") (pintype "passive"))
      (node (ref "C45") (pin "1") (pinfunction "1_1") (pintype "passive"))
      (node (ref "C46") (pin "1") (pinfunction "1_1") (pintype "passive"))
      (node (ref "J16") (pin "3") (pinfunction "3_3") (pintype "passive"))
      (node (ref "U10") (pin "2") (pinfunction "VIN_2") (pintype "passive"))
      (node (ref "U10") (pin "3") (pinfunction "EN_3") (pintype "passive"))
      (node (ref "U11") (pin "2") (pinfunction "VIN_2") (pintype "passive"))
      (node (ref "U11") (pin "3") (pinfunction "EN_3") (pintype "passive"))
      (node (ref "U4") (pin "2") (pinfunction "VIN_2") (pintype "passive"))
      (node (ref "U4") (pin "3") (pinfunction "EN_3") (pintype "passive"))
    )
    (net (code "21") (name "AIN0") (class "Default")
      (node (ref "J10") (pin "5") (pinfunction "5_5") (pintype "passive"))
    )
    (net (code "22") (name "AIN1") (class "Default")
      (node (ref "J10") (pin "6") (pinfunction "6_6") (pintype "passive"))
    )
    (net (code "23") (name "BT-nDis") (class "Default")
      (node (ref "J13") (pin "3") (pinfunction "3_3") (pintype "passive"))
    )
    (net (code "24") (name "CAM-GPIO") (class "Default")
      (node (ref "J23") (pin "9") (pinfunction "9_9") (pintype "passive"))
    )
    (net (code "25") (name "EEPROM-nWP") (class "Default")
      (node (ref "J10") (pin "4") (pinfunction "4_4") (pintype "passive"))
    )
    (net (code "26") (name "GND") (class "Default")
      (node (ref "A1") (pin "3") (pinfunction "GND_3") (pintype "passive"))
      (node (ref "A1") (pin "8") (pinfunction "GND_8") (pintype "passive"))
      (node (ref "A1") (pin "9") (pinfunction "GND_9") (pintype "passive"))
      (node (ref "BATT1") (pin "-") (pinfunction "__-") (pintype "passive"))
      (node (ref "C102") (pin "1") (pinfunction "1_1") (pintype "passive"))
      (node (ref "C118") (pin "2") (pinfunction "2_2") (pintype "passive"))
      (node (ref "C119") (pin "2") (pinfunction "2_2") (pintype "passive"))
      (node (ref "C12") (pin "2") (pinfunction "2_2") (pintype "passive"))
      (node (ref "C120") (pin "2") (pinfunction "2_2") (pintype "passive"))
      (node (ref "C121") (pin "2") (pinfunction "2_2") (pintype "passive"))
      (node (ref "C122") (pin "2") (pinfunction "2_2") (pintype "passive"))
      (node (ref "C13") (pin "2") (pinfunction "2_2") (pintype "passive"))
      (node (ref "C153") (pin "2") (pinfunction "2_2") (pintype "passive"))
      (node (ref "C22") (pin "2") (pinfunction "2_2") (pintype "passive"))
      (node (ref "C23") (pin "2") (pinfunction "2_2") (pintype "passive"))
      (node (ref "C24") (pin "2") (pinfunction "2_2") (pintype "passive"))
      (node (ref "C25") (pin "2") (pinfunction "2_2") (pintype "passive"))
      (node (ref "C26") (pin "2") (pinfunction "2_2") (pintype "passive"))
      (node (ref "C27") (pin "2") (pinfunction "2_2") (pintype "passive"))
      (node (ref "C28") (pin "2") (pinfunction "2_2") (pintype "passive"))
      (node (ref "C30") (pin "2") (pinfunction "2_2") (pintype "passive"))
      (node (ref "C31") (pin "2") (pinfunction "2_2") (pintype "passive"))
      (node (ref "C32") (pin "2") (pinfunction "2_2") (pintype "passive"))
      (node (ref "C33") (pin "2") (pinfunction "2_2") (pintype "passive"))
      (node (ref "C34") (pin "2") (pinfunction "2_2") (pintype "passive"))
      (node (ref "C35") (pin "2") (pinfunction "2_2") (pintype "passive"))
      (node (ref "C38") (pin "2") (pinfunction "2_2") (pintype "passive"))
      (node (ref "C39") (pin "2") (pinfunction "2_2") (pintype "passive"))
      (node (ref "C41") (pin "2") (pinfunction "2_2") (pintype "passive"))
      (node (ref "C42") (pin "2") (pinfunction "2_2") (pintype "passive"))
      (node (ref "C43") (pin "2") (pinfunction "2_2") (pintype "passive"))
      (node (ref "C44") (pin "2") (pinfunction "2_2") (pintype "passive"))
      (node (ref "C45") (pin "2") (pinfunction "2_2") (pintype "passive"))
      (node (ref "C46") (pin "2") (pinfunction "2_2") (pintype "passive"))
      (node (ref "C48") (pin "2") (pinfunction "2_2") (pintype "passive"))
      (node (ref "C49") (pin "2") (pinfunction "2_2") (pintype "passive"))
      (node (ref "C50") (pin "2") (pinfunction "2_2") (pintype "passive"))
      (node (ref "C51") (pin "2") (pinfunction "2_2") (pintype "passive"))
      (node (ref "C52") (pin "2") (pinfunction "2_2") (pintype "passive"))
      (node (ref "C55") (pin "2") (pinfunction "2_2") (pintype "passive"))
      (node (ref "C56") (pin "2") (pinfunction "2_2") (pintype "passive"))
      (node (ref "C71") (pin "2") (pinfunction "2_2") (pintype "passive"))
      (node (ref "C72") (pin "2") (pinfunction "2_2") (pintype "passive"))
      (node (ref "C73") (pin "2") (pinfunction "2_2") (pintype "passive"))
      (node (ref "C94") (pin "1") (pinfunction "1_1") (pintype "passive"))
      (node (ref "D19") (pin "3") (pinfunction "3_3") (pintype "passive"))
      (node (ref "D20") (pin "3") (pinfunction "3_3") (pintype "passive"))
      (node (ref "D5") (pin "2") (pinfunction "2_2") (pintype "passive"))
      (node (ref "FL5") (pin "B1") (pinfunction "GND_B1") (pintype "power_in"))
      (node (ref "J10") (pin "1") (pinfunction "1_1") (pintype "passive"))
      (node (ref "J10") (pin "10") (pinfunction "10_10") (pintype "passive"))
      (node (ref "J10") (pin "12") (pinfunction "12_12") (pintype "passive"))
      (node (ref "J10") (pin "3") (pinfunction "3_3") (pintype "passive"))
      (node (ref "J10") (pin "7") (pinfunction "7_7") (pintype "passive"))
      (node (ref "J11") (pin "1") (pinfunction "1_1") (pintype "passive"))
      (node (ref "J12") (pin "2") (pinfunction "2_2") (pintype "passive"))
      (node (ref "J13") (pin "2") (pinfunction "2_2") (pintype "passive"))
      (node (ref "J14") (pin "15") (pinfunction "GND_15") (pintype "passive"))
      (node (ref "J14") (pin "18") (pinfunction "GND_18") (pintype "passive"))
      (node (ref "J14") (pin "21") (pinfunction "GND_21") (pintype "passive"))
      (node (ref "J14") (pin "26") (pinfunction "GND_26") (pintype "passive"))
      (node (ref "J14") (pin "27") (pinfunction "GND_27") (pintype "passive"))
      (node (ref "J14") (pin "29") (pinfunction "GND_29") (pintype "passive"))
      (node (ref "J14") (pin "34") (pinfunction "GND_34") (pintype "passive"))
      (node (ref "J14") (pin "35") (pinfunction "GND_35") (pintype "passive"))
      (node (ref "J14") (pin "37") (pinfunction "GND_37") (pintype "passive"))
      (node (ref "J14") (pin "4") (pinfunction "GND_4") (pintype "passive"))
      (node (ref "J14") (pin "40") (pinfunction "GND_40") (pintype "passive"))
      (node (ref "J14") (pin "43") (pinfunction "GND_43") (pintype "passive"))
      (node (ref "J14") (pin "50") (pinfunction "GND_50") (pintype "passive"))
      (node (ref "J14") (pin "9") (pinfunction "GND_9") (pintype "passive"))
      (node (ref "J17") (pin "C5") (pinfunction "GND_C5") (pintype "passive"))
      (node (ref "J17") (pin "SH") (pinfunction "SHIELD_SH") (pintype "passive"))
      (node (ref "J2") (pin "6") (pinfunction "6_6") (pintype "passive"))
      (node (ref "J23") (pin "10") (pinfunction "10_10") (pintype "passive"))
      (node (ref "J23") (pin "11") (pinfunction "11_11") (pintype "passive"))
      (node (ref "J23") (pin "12") (pinfunction "12_12") (pintype "passive"))
      (node (ref "J23") (pin "13") (pinfunction "13_13") (pintype "passive"))
      (node (ref "J23") (pin "14") (pinfunction "14_14") (pintype "passive"))
      (node (ref "J23") (pin "5") (pinfunction "5_5") (pintype "passive"))
      (node (ref "J23") (pin "8") (pinfunction "8_8") (pintype "passive"))
      (node (ref "J6") (pin "11") (pinfunction "11_11") (pintype "passive"))
      (node (ref "J6") (pin "27") (pinfunction "27_27") (pintype "passive"))
      (node (ref "J6") (pin "3") (pinfunction "3_3") (pintype "passive"))
      (node (ref "J6") (pin "33") (pinfunction "33_33") (pintype "passive"))
      (node (ref "J6") (pin "39") (pinfunction "39_39") (pintype "passive"))
      (node (ref "J6") (pin "45") (pinfunction "45_45") (pintype "passive"))
      (node (ref "J6") (pin "5") (pinfunction "5_5") (pintype "passive"))
      (node (ref "J6") (pin "51") (pinfunction "51_51") (pintype "passive"))
      (node (ref "J6") (pin "57") (pinfunction "57_57") (pintype "passive"))
      (node (ref "J6") (pin "71") (pinfunction "71_71") (pintype "passive"))
      (node (ref "J6") (pin "73") (pinfunction "73_73") (pintype "passive"))
      (node (ref "J6") (pin "S1") (pinfunction "SHIELD_S1") (pintype "passive"))
      (node (ref "J6") (pin "S2") (pinfunction "SHIELD_S2") (pintype "passive"))
      (node (ref "P2") (pin "4") (pinfunction "4_4") (pintype "passive"))
      (node (ref "R101") (pin "2") (pinfunction "2_2") (pintype "passive"))
      (node (ref "R22") (pin "2") (pinfunction "2_2") (pintype "passive"))
      (node (ref "R29") (pin "2") (pinfunction "2_2") (pintype "passive"))
      (node (ref "R79") (pin "2") (pinfunction "2_2") (pintype "passive"))
      (node (ref "R94") (pin "2") (pinfunction "2_2") (pintype "passive"))
      (node (ref "R98") (pin "2") (pinfunction "2_2") (pintype "passive"))
      (node (ref "U10") (pin "7") (pinfunction "GND_7") (pintype "passive"))
      (node (ref "U10") (pin "9") (pinfunction "EP_9") (pintype "passive"))
      (node (ref "U11") (pin "7") (pinfunction "GND_7") (pintype "passive"))
      (node (ref "U11") (pin "9") (pinfunction "EP_9") (pintype "passive"))
      (node (ref "U22") (pin "5") (pinfunction "GND_5") (pintype "passive"))
      (node (ref "U23") (pin "5") (pinfunction "GND_5") (pintype "passive"))
      (node (ref "U4") (pin "7") (pinfunction "GND_7") (pintype "passive"))
      (node (ref "U4") (pin "9") (pinfunction "EP_9") (pintype "passive"))
      (node (ref "U6") (pin "4") (pinfunction "VSS_4") (pintype "passive"))
      (node (ref "U7") (pin "3") (pinfunction "3_3") (pintype "passive"))
      (node (ref "U8") (pin "3") (pinfunction "3_3") (pintype "passive"))
      (node (ref "U9") (pin "4") (pinfunction "GND_4") (pintype "passive"))
    )
    (net (code "27") (name "Global-EN") (class "Default")
      (node (ref "J10") (pin "14") (pinfunction "14_14") (pintype "passive"))
      (node (ref "J12") (pin "1") (pinfunction "1_1") (pintype "passive"))
      (node (ref "U7") (pin "4") (pinfunction "4_4") (pintype "passive"))
    )
    (net (code "28") (name "HD7_N") (class "Default")
      (node (ref "FL5") (pin "A2") (pinfunction "CH1_IN-_A2") (pintype "passive"))
    )
    (net (code "29") (name "HD7_P") (class "Default")
      (node (ref "FL5") (pin "A1") (pinfunction "CH1_IN+_A1") (pintype "passive"))
    )
    (net (code "30") (name "ID-SC") (class "Default")
      (node (ref "J23") (pin "1") (pinfunction "1_1") (pintype "passive"))
    )
    (net (code "31") (name "ID-SD") (class "Default")
      (node (ref "J23") (pin "3") (pinfunction "3_3") (pintype "passive"))
    )
    (net (code "32") (name "IO4") (class "Default")
      (node (ref "U23") (pin "4") (pinfunction "DI_4") (pintype "passive"))
    )
    (net (code "33") (name "IO5") (class "Default")
      (node (ref "U23") (pin "1") (pinfunction "RO_1") (pintype "passive"))
    )
    (net (code "34") (name "IO8") (class "Default")
      (node (ref "U22") (pin "4") (pinfunction "DI_4") (pintype "passive"))
    )
    (net (code "35") (name "IO9") (class "Default")
      (node (ref "U22") (pin "1") (pinfunction "RO_1") (pintype "passive"))
    )
    (net (code "36") (name "IO10") (class "Default")
      (node (ref "U22") (pin "2") (pinfunction "POL_2") (pintype "passive"))
      (node (ref "U22") (pin "3") (pinfunction "DE_3") (pintype "passive"))
    )
    (net (code "37") (name "IO11") (class "Default")
      (node (ref "U23") (pin "2") (pinfunction "POL_2") (pintype "passive"))
      (node (ref "U23") (pin "3") (pinfunction "DE_3") (pintype "passive"))
    )
    (net (code "38") (name "IO13") (class "Default")
      (node (ref "J23") (pin "7") (pinfunction "7_7") (pintype "passive"))
    )
    (net (code "39") (name "IO14") (class "Default")
      (node (ref "J14") (pin "11") (pinfunction "UART_RX_11") (pintype "passive"))
    )
    (net (code "40") (name "IO15") (class "Default")
      (node (ref "J14") (pin "13") (pinfunction "UART_TX_13") (pintype "passive"))
    )
    (net (code "41") (name "IO16") (class "Default")
      (node (ref "J14") (pin "23") (pinfunction "UART_CTS_23") (pintype "passive"))
    )
    (net (code "42") (name "IO17") (class "Default")
      (node (ref "J14") (pin "25") (pinfunction "UART_RTS_25") (pintype "passive"))
    )
    (net (code "43") (name "M.2_OFF{slash}ON") (class "Default")
      (node (ref "J6") (pin "6") (pinfunction "6_6") (pintype "passive"))
    )
    (net (code "44") (name "M.2_RST") (class "Default")
      (node (ref "R80") (pin "2") (pinfunction "2_2") (pintype "passive"))
    )
    (net (code "45") (name "M.2_W_DIS") (class "Default")
      (node (ref "J6") (pin "8") (pinfunction "8_8") (pintype "passive"))
    )
    (net (code "46") (name "Net-(BATT1-Pad+)") (class "Default")
      (node (ref "BATT1") (pin "+") (pinfunction "+_+") (pintype "passive"))
      (node (ref "D6") (pin "1") (pinfunction "1_1") (pintype "passive"))
    )
    (net (code "47") (name "Net-(C18-Pad2)") (class "Default")
      (node (ref "C18") (pin "2") (pinfunction "2_2") (pintype "passive"))
      (node (ref "R17") (pin "1") (pinfunction "1_1") (pintype "passive"))
      (node (ref "U7") (pin "2") (pinfunction "2_2") (pintype "passive"))
    )
    (net (code "48") (name "Net-(C38-Pad1)") (class "Default")
      (node (ref "C38") (pin "1") (pinfunction "1_1") (pintype "passive"))
      (node (ref "R24") (pin "2") (pinfunction "2_2") (pintype "passive"))
    )
    (net (code "49") (name "Net-(C52-Pad1)") (class "Default")
      (node (ref "C52") (pin "1") (pinfunction "1_1") (pintype "passive"))
      (node (ref "R27") (pin "2") (pinfunction "2_2") (pintype "passive"))
    )
    (net (code "50") (name "Net-(C55-Pad1)") (class "Default")
      (node (ref "C55") (pin "1") (pinfunction "1_1") (pintype "passive"))
      (node (ref "R30") (pin "2") (pinfunction "2_2") (pintype "passive"))
    )
    (net (code "51") (name "Net-(D5-Pad1)") (class "Default")
      (node (ref "D5") (pin "1") (pinfunction "1_1") (pintype "passive"))
      (node (ref "R15") (pin "1") (pinfunction "1_1") (pintype "passive"))
    )
    (net (code "52") (name "Net-(D13-C)") (class "Default")
      (node (ref "D13") (pin "2") (pinfunction "C_2") (pintype "passive"))
      (node (ref "R77") (pin "2") (pinfunction "2_2") (pintype "passive"))
    )
    (net (code "53") (name "Net-(D16-C)") (class "Default")
      (node (ref "D16") (pin "2") (pinfunction "C_2") (pintype "passive"))
      (node (ref "R81") (pin "2") (pinfunction "2_2") (pintype "passive"))
    )
    (net (code "54") (name "Net-(J6-Pad67)") (class "Default")
      (node (ref "J6") (pin "67") (pinfunction "67_67") (pintype "passive"))
      (node (ref "R80") (pin "1") (pinfunction "1_1") (pintype "passive"))
    )
    (net (code "55") (name "Net-(J6-Pad75)") (class "Default")
      (node (ref "J6") (pin "75") (pinfunction "75_75") (pintype "passive"))
      (node (ref "R79") (pin "1") (pinfunction "1_1") (pintype "passive"))
    )
    (net (code "56") (name "Net-(J10-Pad13)") (class "Default")
      (node (ref "J10") (pin "13") (pinfunction "13_13") (pintype "passive"))
      (node (ref "U8") (pin "4") (pinfunction "4_4") (pintype "passive"))
    )
    (net (code "57") (name "Net-(J11-Pad2)") (class "Default")
      (node (ref "J11") (pin "2") (pinfunction "2_2") (pintype "passive"))
      (node (ref "J16") (pin "2") (pinfunction "2_2") (pintype "passive"))
    )
    (net (code "58") (name "Net-(J14-RI)") (class "Default")
      (node (ref "J14") (pin "17") (pinfunction "RI_17") (pintype "passive"))
      (node (ref "R88") (pin "1") (pinfunction "1_1") (pintype "passive"))
    )
    (net (code "59") (name "Net-(J17-VPP)") (class "Default")
      (node (ref "C122") (pin "1") (pinfunction "1_1") (pintype "passive"))
      (node (ref "J17") (pin "C6") (pinfunction "VPP_C6") (pintype "passive"))
    )
    (net (code "60") (name "Net-(U4-BST)") (class "Default")
      (node (ref "C11") (pin "2") (pinfunction "2_2") (pintype "passive"))
      (node (ref "U4") (pin "1") (pinfunction "BST_1") (pintype "passive"))
    )
    (net (code "61") (name "Net-(U4-COMP)") (class "Default")
      (node (ref "R27") (pin "1") (pinfunction "1_1") (pintype "passive"))
      (node (ref "U4") (pin "6") (pinfunction "COMP_6") (pintype "passive"))
    )
    (net (code "62") (name "Net-(U4-FB)") (class "Default")
      (node (ref "R101") (pin "1") (pinfunction "1_1") (pintype "passive"))
      (node (ref "R20") (pin "2") (pinfunction "2_2") (pintype "passive"))
      (node (ref "U4") (pin "5") (pinfunction "FB_5") (pintype "passive"))
    )
    (net (code "63") (name "Net-(U4-SS)") (class "Default")
      (node (ref "C48") (pin "1") (pinfunction "1_1") (pintype "passive"))
      (node (ref "U4") (pin "4") (pinfunction "SS_4") (pintype "passive"))
    )
    (net (code "64") (name "Net-(U4-SW)") (class "Default")
      (node (ref "C11") (pin "1") (pinfunction "1_1") (pintype "passive"))
      (node (ref "L1") (pin "2") (pinfunction "2_2") (pintype "passive"))
      (node (ref "U4") (pin "8") (pinfunction "SW_8") (pintype "passive"))
    )
    (net (code "65") (name "Net-(U6-OSCI)") (class "Default")
      (node (ref "U6") (pin "1") (pinfunction "OSCI_1") (pintype "passive"))
      (node (ref "X2") (pin "2") (pinfunction "2_2") (pintype "passive"))
    )
    (net (code "66") (name "Net-(U6-OSCIO)") (class "Default")
      (node (ref "U6") (pin "2") (pinfunction "OSCIO_2") (pintype "passive"))
      (node (ref "X2") (pin "1") (pinfunction "1_1") (pintype "passive"))
    )
    (net (code "67") (name "Net-(U6-VDD)") (class "Default")
      (node (ref "C22") (pin "1") (pinfunction "1_1") (pintype "passive"))
      (node (ref "D6") (pin "3") (pinfunction "3_3") (pintype "passive"))
      (node (ref "U6") (pin "8") (pinfunction "VDD_8") (pintype "passive"))
    )
    (net (code "68") (name "Net-(U9-PWM)") (class "Default")
      (node (ref "J11") (pin "4") (pinfunction "4_4") (pintype "passive"))
      (node (ref "U9") (pin "5") (pinfunction "PWM_5") (pintype "passive"))
    )
    (net (code "69") (name "Net-(U9-TACH)") (class "Default")
      (node (ref "J11") (pin "3") (pinfunction "3_3") (pintype "passive"))
      (node (ref "R19") (pin "2") (pinfunction "2_2") (pintype "passive"))
      (node (ref "U9") (pin "6") (pinfunction "TACH_6") (pintype "passive"))
    )
    (net (code "70") (name "Net-(U10-BST)") (class "Default")
      (node (ref "C29") (pin "2") (pinfunction "2_2") (pintype "passive"))
      (node (ref "U10") (pin "1") (pinfunction "BST_1") (pintype "passive"))
    )
    (net (code "71") (name "Net-(U10-COMP)") (class "Default")
      (node (ref "R24") (pin "1") (pinfunction "1_1") (pintype "passive"))
      (node (ref "U10") (pin "6") (pinfunction "COMP_6") (pintype "passive"))
    )
    (net (code "72") (name "Net-(U10-FB)") (class "Default")
      (node (ref "R21") (pin "2") (pinfunction "2_2") (pintype "passive"))
      (node (ref "R22") (pin "1") (pinfunction "1_1") (pintype "passive"))
      (node (ref "U10") (pin "5") (pinfunction "FB_5") (pintype "passive"))
    )
    (net (code "73") (name "Net-(U10-SS)") (class "Default")
      (node (ref "C39") (pin "1") (pinfunction "1_1") (pintype "passive"))
      (node (ref "U10") (pin "4") (pinfunction "SS_4") (pintype "passive"))
    )
    (net (code "74") (name "Net-(U10-SW)") (class "Default")
      (node (ref "C29") (pin "1") (pinfunction "1_1") (pintype "passive"))
      (node (ref "L2") (pin "2") (pinfunction "2_2") (pintype "passive"))
      (node (ref "U10") (pin "8") (pinfunction "SW_8") (pintype "passive"))
    )
    (net (code "75") (name "Net-(U11-BST)") (class "Default")
      (node (ref "C47") (pin "2") (pinfunction "2_2") (pintype "passive"))
      (node (ref "U11") (pin "1") (pinfunction "BST_1") (pintype "passive"))
    )
    (net (code "76") (name "Net-(U11-COMP)") (class "Default")
      (node (ref "R30") (pin "1") (pinfunction "1_1") (pintype "passive"))
      (node (ref "U11") (pin "6") (pinfunction "COMP_6") (pintype "passive"))
    )
    (net (code "77") (name "Net-(U11-FB)") (class "Default")
      (node (ref "R28") (pin "2") (pinfunction "2_2") (pintype "passive"))
      (node (ref "R29") (pin "1") (pinfunction "1_1") (pintype "passive"))
      (node (ref "U11") (pin "5") (pinfunction "FB_5") (pintype "passive"))
    )
    (net (code "78") (name "Net-(U11-SS)") (class "Default")
      (node (ref "C56") (pin "1") (pinfunction "1_1") (pintype "passive"))
      (node (ref "U11") (pin "4") (pinfunction "SS_4") (pintype "passive"))
    )
    (net (code "79") (name "Net-(U11-SW)") (class "Default")
      (node (ref "C47") (pin "1") (pinfunction "1_1") (pintype "passive"))
      (node (ref "L3") (pin "2") (pinfunction "2_2") (pintype "passive"))
      (node (ref "U11") (pin "8") (pinfunction "SW_8") (pintype "passive"))
    )
    (net (code "80") (name "Net-(U22-A)") (class "Default")
      (node (ref "R91") (pin "1") (pinfunction "1_1") (pintype "passive"))
      (node (ref "R92") (pin "1") (pinfunction "1_1") (pintype "passive"))
      (node (ref "U22") (pin "6") (pinfunction "A_6") (pintype "passive"))
    )
    (net (code "81") (name "Net-(U22-B)") (class "Default")
      (node (ref "R93") (pin "1") (pinfunction "1_1") (pintype "passive"))
      (node (ref "R94") (pin "1") (pinfunction "1_1") (pintype "passive"))
      (node (ref "U22") (pin "7") (pinfunction "B_7") (pintype "passive"))
    )
    (net (code "82") (name "Net-(U23-A)") (class "Default")
      (node (ref "R95") (pin "1") (pinfunction "1_1") (pintype "passive"))
      (node (ref "R96") (pin "1") (pinfunction "1_1") (pintype "passive"))
      (node (ref "U23") (pin "6") (pinfunction "A_6") (pintype "passive"))
    )
    (net (code "83") (name "Net-(U23-B)") (class "Default")
      (node (ref "R97") (pin "1") (pinfunction "1_1") (pintype "passive"))
      (node (ref "R98") (pin "1") (pinfunction "1_1") (pintype "passive"))
      (node (ref "U23") (pin "7") (pinfunction "B_7") (pintype "passive"))
    )
    (net (code "84") (name "RUN-PG") (class "Default")
      (node (ref "J12") (pin "3") (pinfunction "3_3") (pintype "passive"))
      (node (ref "U8") (pin "2") (pinfunction "2_2") (pintype "passive"))
    )
    (net (code "85") (name "SCL0") (class "Default")
      (node (ref "U9") (pin "2") (pinfunction "SCL_2") (pintype "passive"))
    )
    (net (code "86") (name "SCL1") (class "Default")
      (node (ref "A1") (pin "4") (pinfunction "SDA/SDI_4") (pintype "passive"))
      (node (ref "R32") (pin "2") (pinfunction "2_2") (pintype "passive"))
    )
    (net (code "87") (name "SCL6") (class "Default")
      (node (ref "P2") (pin "2") (pinfunction "2_2") (pintype "passive"))
      (node (ref "U6") (pin "6") (pinfunction "SCL_6") (pintype "passive"))
    )
    (net (code "88") (name "SDA0") (class "Default")
      (node (ref "U9") (pin "1") (pinfunction "SDA_1") (pintype "passive"))
    )
    (net (code "89") (name "SDA1") (class "Default")
      (node (ref "A1") (pin "2") (pinfunction "SCL/SCLK_2") (pintype "passive"))
      (node (ref "R33") (pin "2") (pinfunction "2_2") (pintype "passive"))
    )
    (net (code "90") (name "SDA6") (class "Default")
      (node (ref "P2") (pin "1") (pinfunction "1_1") (pintype "passive"))
      (node (ref "U6") (pin "5") (pinfunction "SDA_5") (pintype "passive"))
    )
    (net (code "91") (name "SYNC-IN") (class "Default")
      (node (ref "J10") (pin "8") (pinfunction "8_8") (pintype "passive"))
    )
    (net (code "92") (name "SYNC-OUT") (class "Default")
      (node (ref "J10") (pin "9") (pinfunction "9_9") (pintype "passive"))
    )
    (net (code "93") (name "TV-OUT") (class "Default")
      (node (ref "J10") (pin "11") (pinfunction "11_11") (pintype "passive"))
    )
    (net (code "94") (name "T{slash}R") (class "Default")
      (node (ref "R88") (pin "2") (pinfunction "2_2") (pintype "passive"))
    )
    (net (code "95") (name "WL-nDis") (class "Default")
      (node (ref "J13") (pin "1") (pinfunction "1_1") (pintype "passive"))
    )
    (net (code "96") (name "nRPI-BOOT") (class "Default")
      (node (ref "J10") (pin "2") (pinfunction "2_2") (pintype "passive"))
    )
    (net (code "97") (name "unconnected-(A1-INT{slash}SDO-Pad7)") (class "Default")
      (node (ref "A1") (pin "7") (pinfunction "INT/SDO_7") (pintype "passive+no_connect"))
    )
    (net (code "98") (name "unconnected-(A1-NC-Pad1)") (class "Default")
      (node (ref "A1") (pin "1") (pinfunction "NC_1") (pintype "passive+no_connect"))
    )
    (net (code "99") (name "unconnected-(A1-NC-Pad5)") (class "Default")
      (node (ref "A1") (pin "5") (pinfunction "NC_5") (pintype "passive+no_connect"))
    )
    (net (code "100") (name "unconnected-(A1-~{CS}-Pad6)") (class "Default")
      (node (ref "A1") (pin "6") (pinfunction "~{CS}_6") (pintype "passive+no_connect"))
    )
    (net (code "101") (name "unconnected-(J6-Pad1)") (class "Default")
      (node (ref "J6") (pin "1") (pinfunction "1_1") (pintype "passive+no_connect"))
    )
    (net (code "102") (name "unconnected-(J6-Pad20)") (class "Default")
      (node (ref "J6") (pin "20") (pinfunction "20_20") (pintype "passive+no_connect"))
    )
    (net (code "103") (name "unconnected-(J6-Pad21)") (class "Default")
      (node (ref "J6") (pin "21") (pinfunction "21_21") (pintype "passive+no_connect"))
    )
    (net (code "104") (name "unconnected-(J6-Pad22)") (class "Default")
      (node (ref "J6") (pin "22") (pinfunction "22_22") (pintype "passive+no_connect"))
    )
    (net (code "105") (name "unconnected-(J6-Pad23)") (class "Default")
      (node (ref "J6") (pin "23") (pinfunction "23_23") (pintype "passive+no_connect"))
    )
    (net (code "106") (name "unconnected-(J6-Pad24)") (class "Default")
      (node (ref "J6") (pin "24") (pinfunction "24_24") (pintype "passive+no_connect"))
    )
    (net (code "107") (name "unconnected-(J6-Pad25)") (class "Default")
      (node (ref "J6") (pin "25") (pinfunction "25_25") (pintype "passive+no_connect"))
    )
    (net (code "108") (name "unconnected-(J6-Pad26)") (class "Default")
      (node (ref "J6") (pin "26") (pinfunction "26_26") (pintype "passive+no_connect"))
    )
    (net (code "109") (name "unconnected-(J6-Pad28)") (class "Default")
      (node (ref "J6") (pin "28") (pinfunction "28_28") (pintype "passive+no_connect"))
    )
    (net (code "110") (name "unconnected-(J6-Pad29)") (class "Default")
      (node (ref "J6") (pin "29") (pinfunction "29_29") (pintype "passive+no_connect"))
    )
    (net (code "111") (name "unconnected-(J6-Pad31)") (class "Default")
      (node (ref "J6") (pin "31") (pinfunction "31_31") (pintype "passive+no_connect"))
    )
    (net (code "112") (name "unconnected-(J6-Pad35)") (class "Default")
      (node (ref "J6") (pin "35") (pinfunction "35_35") (pintype "passive+no_connect"))
    )
    (net (code "113") (name "unconnected-(J6-Pad37)") (class "Default")
      (node (ref "J6") (pin "37") (pinfunction "37_37") (pintype "passive+no_connect"))
    )
    (net (code "114") (name "unconnected-(J6-Pad38)") (class "Default")
      (node (ref "J6") (pin "38") (pinfunction "38_38") (pintype "passive+no_connect"))
    )
    (net (code "115") (name "unconnected-(J6-Pad40)") (class "Default")
      (node (ref "J6") (pin "40") (pinfunction "40_40") (pintype "passive+no_connect"))
    )
    (net (code "116") (name "unconnected-(J6-Pad41)") (class "Default")
      (node (ref "J6") (pin "41") (pinfunction "41_41") (pintype "passive+no_connect"))
    )
    (net (code "117") (name "unconnected-(J6-Pad42)") (class "Default")
      (node (ref "J6") (pin "42") (pinfunction "42_42") (pintype "passive+no_connect"))
    )
    (net (code "118") (name "unconnected-(J6-Pad43)") (class "Default")
      (node (ref "J6") (pin "43") (pinfunction "43_43") (pintype "passive+no_connect"))
    )
    (net (code "119") (name "unconnected-(J6-Pad44)") (class "Default")
      (node (ref "J6") (pin "44") (pinfunction "44_44") (pintype "passive+no_connect"))
    )
    (net (code "120") (name "unconnected-(J6-Pad46)") (class "Default")
      (node (ref "J6") (pin "46") (pinfunction "46_46") (pintype "passive+no_connect"))
    )
    (net (code "121") (name "unconnected-(J6-Pad47)") (class "Default")
      (node (ref "J6") (pin "47") (pinfunction "47_47") (pintype "passive+no_connect"))
    )
    (net (code "122") (name "unconnected-(J6-Pad48)") (class "Default")
      (node (ref "J6") (pin "48") (pinfunction "48_48") (pintype "passive+no_connect"))
    )
    (net (code "123") (name "unconnected-(J6-Pad49)") (class "Default")
      (node (ref "J6") (pin "49") (pinfunction "49_49") (pintype "passive+no_connect"))
    )
    (net (code "124") (name "unconnected-(J6-Pad50)") (class "Default")
      (node (ref "J6") (pin "50") (pinfunction "50_50") (pintype "passive+no_connect"))
    )
    (net (code "125") (name "unconnected-(J6-Pad52)") (class "Default")
      (node (ref "J6") (pin "52") (pinfunction "52_52") (pintype "passive+no_connect"))
    )
    (net (code "126") (name "unconnected-(J6-Pad53)") (class "Default")
      (node (ref "J6") (pin "53") (pinfunction "53_53") (pintype "passive+no_connect"))
    )
    (net (code "127") (name "unconnected-(J6-Pad54)") (class "Default")
      (node (ref "J6") (pin "54") (pinfunction "54_54") (pintype "passive+no_connect"))
    )
    (net (code "128") (name "unconnected-(J6-Pad55)") (class "Default")
      (node (ref "J6") (pin "55") (pinfunction "55_55") (pintype "passive+no_connect"))
    )
    (net (code "129") (name "unconnected-(J6-Pad56)") (class "Default")
      (node (ref "J6") (pin "56") (pinfunction "56_56") (pintype "passive+no_connect"))
    )
    (net (code "130") (name "unconnected-(J6-Pad58)") (class "Default")
      (node (ref "J6") (pin "58") (pinfunction "58_58") (pintype "passive+no_connect"))
    )
    (net (code "131") (name "unconnected-(J6-Pad59)") (class "Default")
      (node (ref "J6") (pin "59") (pinfunction "59_59") (pintype "passive+no_connect"))
    )
    (net (code "132") (name "unconnected-(J6-Pad60)") (class "Default")
      (node (ref "J6") (pin "60") (pinfunction "60_60") (pintype "passive+no_connect"))
    )
    (net (code "133") (name "unconnected-(J6-Pad61)") (class "Default")
      (node (ref "J6") (pin "61") (pinfunction "61_61") (pintype "passive+no_connect"))
    )
    (net (code "134") (name "unconnected-(J6-Pad62)") (class "Default")
      (node (ref "J6") (pin "62") (pinfunction "62_62") (pintype "passive+no_connect"))
    )
    (net (code "135") (name "unconnected-(J6-Pad63)") (class "Default")
      (node (ref "J6") (pin "63") (pinfunction "63_63") (pintype "passive+no_connect"))
    )
    (net (code "136") (name "unconnected-(J6-Pad64)") (class "Default")
      (node (ref "J6") (pin "64") (pinfunction "64_64") (pintype "passive+no_connect"))
    )
    (net (code "137") (name "unconnected-(J6-Pad65)") (class "Default")
      (node (ref "J6") (pin "65") (pinfunction "65_65") (pintype "passive+no_connect"))
    )
    (net (code "138") (name "unconnected-(J6-Pad68)") (class "Default")
      (node (ref "J6") (pin "68") (pinfunction "68_68") (pintype "passive+no_connect"))
    )
    (net (code "139") (name "unconnected-(J6-Pad69)") (class "Default")
      (node (ref "J6") (pin "69") (pinfunction "69_69") (pintype "passive+no_connect"))
    )
    (net (code "140") (name "unconnected-(J14-DTR-Pad31)") (class "Default")
      (node (ref "J14") (pin "31") (pinfunction "DTR_31") (pintype "passive+no_connect"))
    )
    (net (code "141") (name "unconnected-(J14-I2C_SCL-Pad30)") (class "Default")
      (node (ref "J14") (pin "30") (pinfunction "I2C_SCL_30") (pintype "passive+no_connect"))
    )
    (net (code "142") (name "unconnected-(J14-I2C_SDA-Pad32)") (class "Default")
      (node (ref "J14") (pin "32") (pinfunction "I2C_SDA_32") (pintype "passive+no_connect"))
    )
    (net (code "143") (name "unconnected-(J14-NC-Pad6)") (class "Default")
      (node (ref "J14") (pin "6") (pinfunction "NC_6") (pintype "passive+no_connect"))
    )
    (net (code "144") (name "unconnected-(J14-NC-Pad28)") (class "Default")
      (node (ref "J14") (pin "28") (pinfunction "NC_28") (pintype "passive+no_connect"))
    )
    (net (code "145") (name "unconnected-(J14-NC-Pad48)") (class "Default")
      (node (ref "J14") (pin "48") (pinfunction "NC_48") (pintype "passive+no_connect"))
    )
    (net (code "146") (name "unconnected-(J14-PCM_CLK-Pad45)") (class "Default")
      (node (ref "J14") (pin "45") (pinfunction "PCM_CLK_45") (pintype "passive+no_connect"))
    )
    (net (code "147") (name "unconnected-(J14-PCM_DI-Pad49)") (class "Default")
      (node (ref "J14") (pin "49") (pinfunction "PCM_DI_49") (pintype "passive+no_connect"))
    )
    (net (code "148") (name "unconnected-(J14-PCM_DOUT-Pad47)") (class "Default")
      (node (ref "J14") (pin "47") (pinfunction "PCM_DOUT_47") (pintype "passive+no_connect"))
    )
    (net (code "149") (name "unconnected-(J14-PCM_SYNC-Pad51)") (class "Default")
      (node (ref "J14") (pin "51") (pinfunction "PCM_SYNC_51") (pintype "passive+no_connect"))
    )
    (net (code "150") (name "unconnected-(J14-PERST#-Pad22)") (class "Default")
      (node (ref "J14") (pin "22") (pinfunction "PERST#_22") (pintype "passive+no_connect"))
    )
    (net (code "151") (name "unconnected-(J14-RESERVED-Pad3)") (class "Default")
      (node (ref "J14") (pin "3") (pinfunction "RESERVED_3") (pintype "passive+no_connect"))
    )
    (net (code "152") (name "unconnected-(J14-RESERVED-Pad5)") (class "Default")
      (node (ref "J14") (pin "5") (pinfunction "RESERVED_5") (pintype "passive+no_connect"))
    )
    (net (code "153") (name "unconnected-(J14-RESERVED-Pad7)") (class "Default")
      (node (ref "J14") (pin "7") (pinfunction "RESERVED_7") (pintype "passive+no_connect"))
    )
    (net (code "154") (name "unconnected-(J14-RESERVED-Pad16)") (class "Default")
      (node (ref "J14") (pin "16") (pinfunction "RESERVED_16") (pintype "passive+no_connect"))
    )
    (net (code "155") (name "unconnected-(J14-RESERVED-Pad19)") (class "Default")
      (node (ref "J14") (pin "19") (pinfunction "RESERVED_19") (pintype "passive+no_connect"))
    )
    (net (code "156") (name "unconnected-(J14-RESERVED-Pad24)") (class "Default")
      (node (ref "J14") (pin "24") (pinfunction "RESERVED_24") (pintype "passive+no_connect"))
    )
    (net (code "157") (name "unconnected-(J14-RESERVED-Pad33)") (class "Default")
      (node (ref "J14") (pin "33") (pinfunction "RESERVED_33") (pintype "passive+no_connect"))
    )
    (net (code "158") (name "unconnected-(J14-RESERVED-Pad46)") (class "Default")
      (node (ref "J14") (pin "46") (pinfunction "RESERVED_46") (pintype "passive+no_connect"))
    )
    (net (code "159") (name "unconnected-(J14-USB_DM-Pad36)") (class "Default")
      (node (ref "J14") (pin "36") (pinfunction "USB_DM_36") (pintype "passive+no_connect"))
    )
    (net (code "160") (name "unconnected-(J14-USB_DP-Pad38)") (class "Default")
      (node (ref "J14") (pin "38") (pinfunction "USB_DP_38") (pintype "passive+no_connect"))
    )
    (net (code "161") (name "unconnected-(J14-USIM_CLK-Pad12)") (class "Default")
      (node (ref "J14") (pin "12") (pinfunction "USIM_CLK_12") (pintype "passive+no_connect"))
    )
    (net (code "162") (name "unconnected-(J14-USIM_DATA-Pad10)") (class "Default")
      (node (ref "J14") (pin "10") (pinfunction "USIM_DATA_10") (pintype "passive+no_connect"))
    )
    (net (code "163") (name "unconnected-(J14-USIM_PRESENCE-Pad44)") (class "Default")
      (node (ref "J14") (pin "44") (pinfunction "USIM_PRESENCE_44") (pintype "passive+no_connect"))
    )
    (net (code "164") (name "unconnected-(J14-USIM_RST-Pad14)") (class "Default")
      (node (ref "J14") (pin "14") (pinfunction "USIM_RST_14") (pintype "passive+no_connect"))
    )
    (net (code "165") (name "unconnected-(J14-USIM_VDD-Pad8)") (class "Default")
      (node (ref "J14") (pin "8") (pinfunction "USIM_VDD_8") (pintype "passive+no_connect"))
    )
    (net (code "166") (name "unconnected-(J14-WAKE#-Pad1)") (class "Default")
      (node (ref "J14") (pin "1") (pinfunction "WAKE#_1") (pintype "passive+no_connect"))
    )
    (net (code "167") (name "unconnected-(J14-W_DISABLE#-Pad20)") (class "Default")
      (node (ref "J14") (pin "20") (pinfunction "W_DISABLE#_20") (pintype "passive+no_connect"))
    )
    (net (code "168") (name "unconnected-(U6-CLKO-Pad7)") (class "Default")
      (node (ref "U6") (pin "7") (pinfunction "CLKO_7") (pintype "passive+no_connect"))
    )
    (net (code "169") (name "unconnected-(U7-Pad1)") (class "Default")
      (node (ref "U7") (pin "1") (pinfunction "1_1") (pintype "passive+no_connect"))
    )
    (net (code "170") (name "unconnected-(U8-Pad1)") (class "Default")
      (node (ref "U8") (pin "1") (pinfunction "1_1") (pintype "passive+no_connect"))
    )
    (net (code "171") (name "unconnected-(U9-CLK-Pad7)") (class "Default")
      (node (ref "U9") (pin "7") (pinfunction "CLK_7") (pintype "passive+no_connect"))
    )
    (net (code "172") (name "unconnected-(U9-nALERT-Pad8)") (class "Default")
      (node (ref "U9") (pin "8") (pinfunction "nALERT_8") (pintype "passive+no_connect"))
    )
  )
)
